# input_filter.net
KiCad netlist of a schematic drawn in Altium Designer
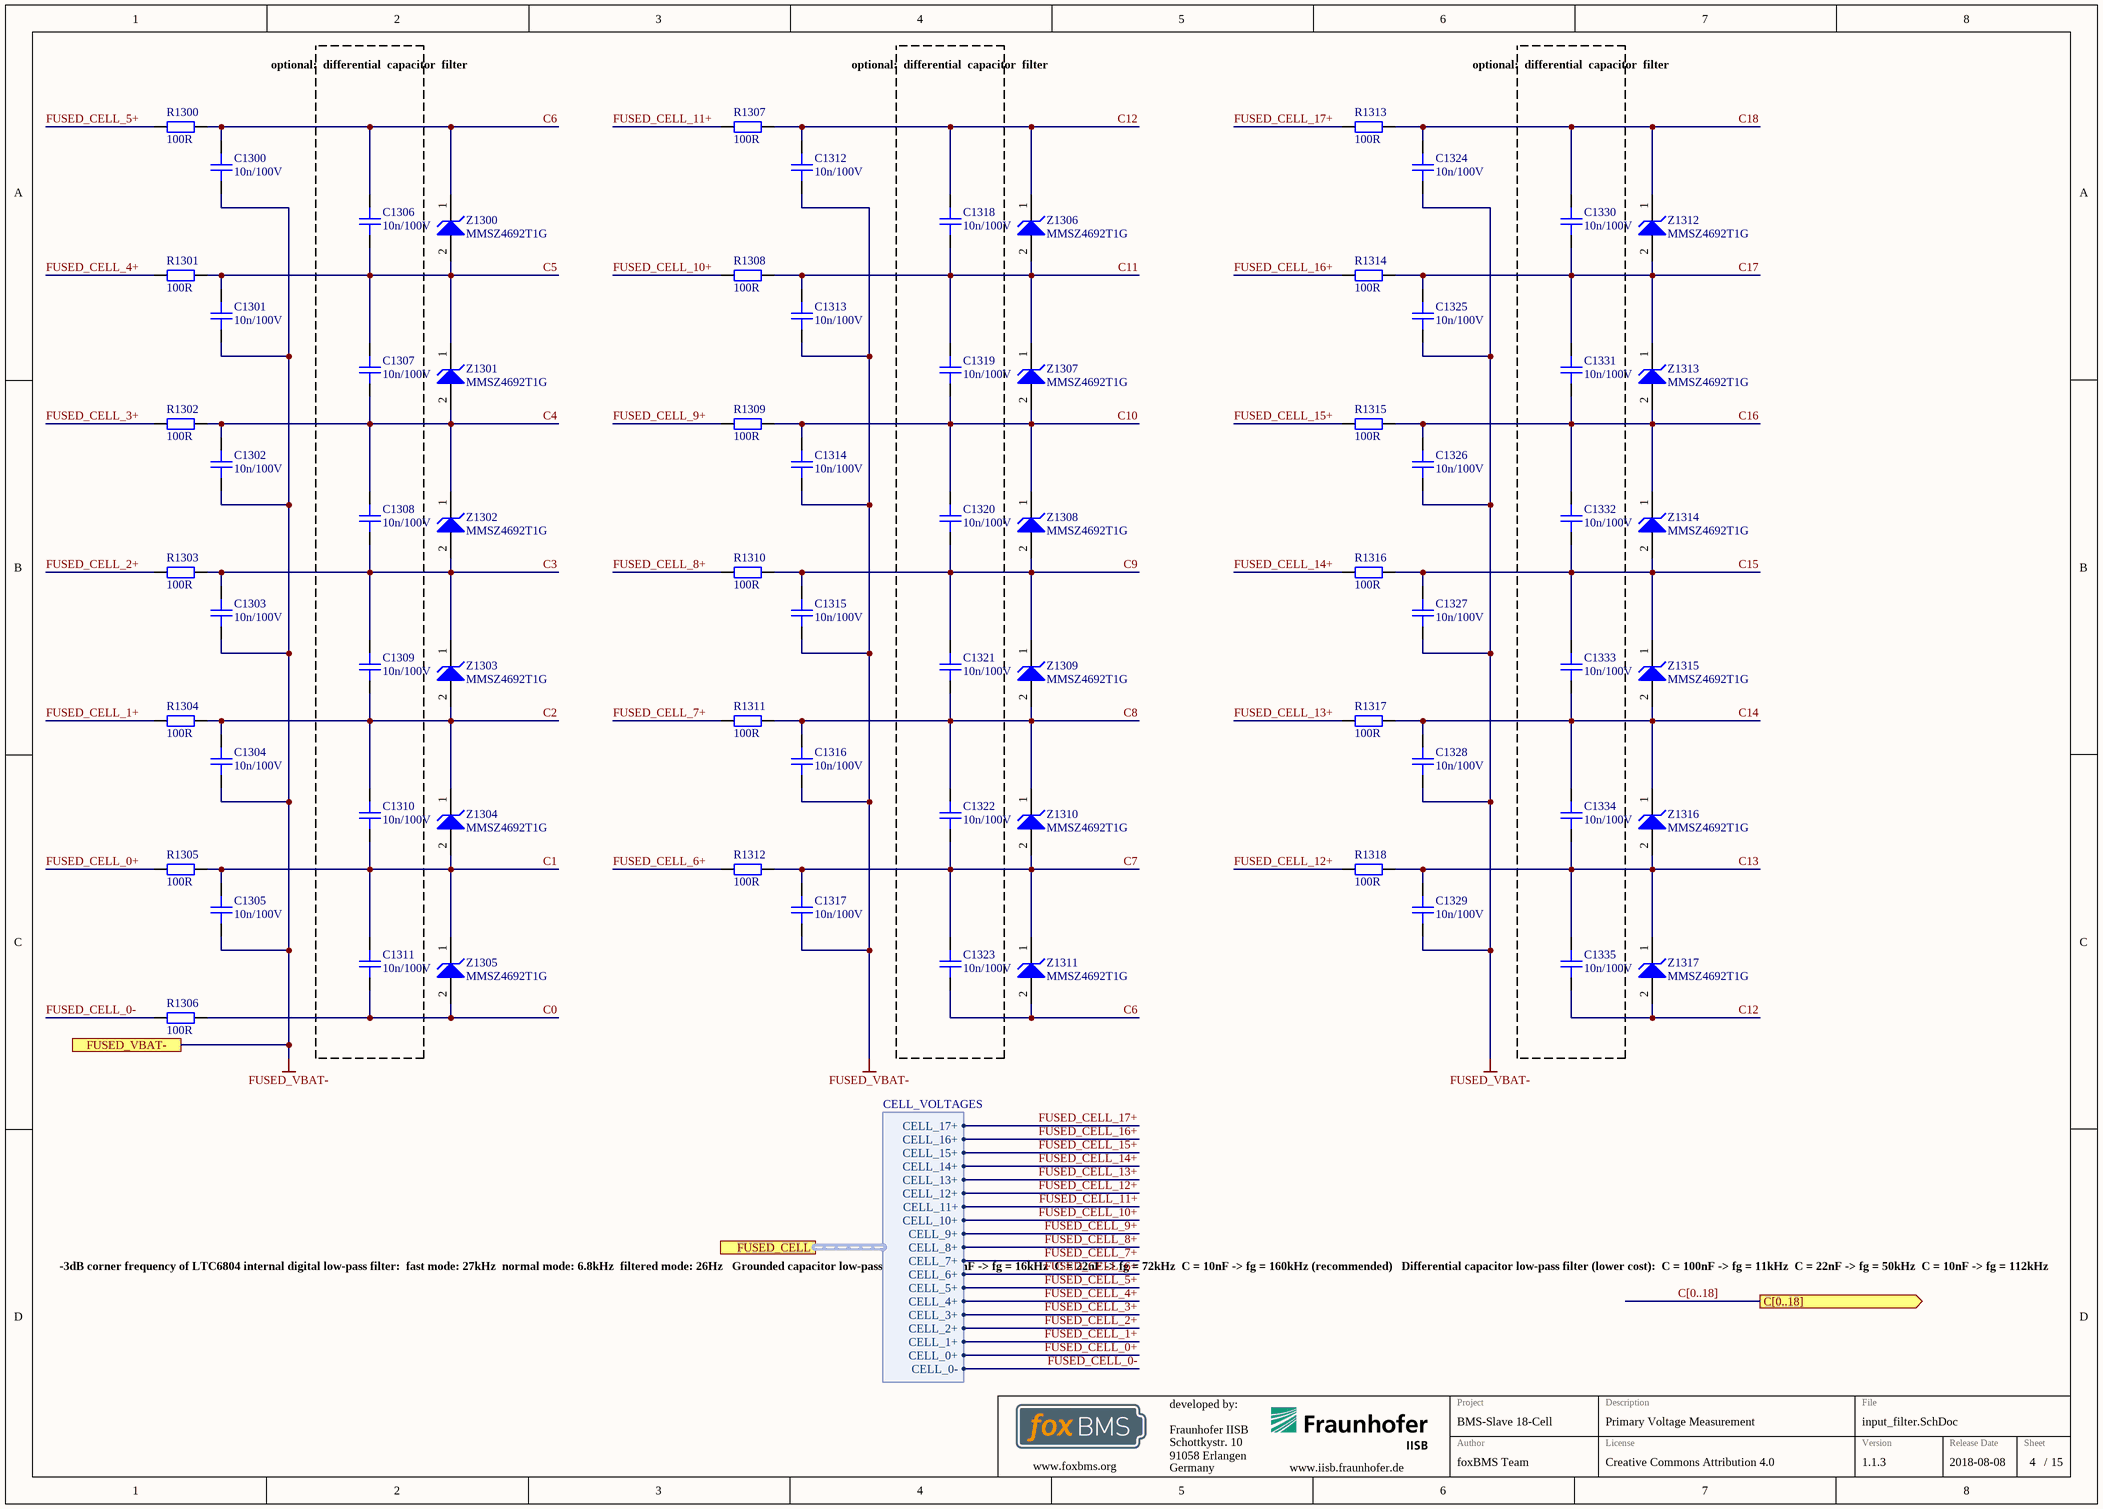
[diagram p0: input_filter.SchDoc]

(export (version "E")
  (design (tool "Eeschema 10.0.6"))
  (components
    (comp (ref "C1300")
      (value "10n/100V")
      (footprint "CAPC1608X08N")
      (description "MLCC")
      (fields (field (name "PART NUMBER") "gen_C_ceramic_10n_100V_X7R_0603"))
      (libsource (lib "OE750") (part "C"))
    )
    (comp (ref "C1301")
      (value "10n/100V")
      (footprint "CAPC1608X08N")
      (description "MLCC")
      (fields (field (name "PART NUMBER") "gen_C_ceramic_10n_100V_X7R_0603"))
      (libsource (lib "OE750") (part "C"))
    )
    (comp (ref "C1302")
      (value "10n/100V")
      (footprint "CAPC1608X08N")
      (description "MLCC")
      (fields (field (name "PART NUMBER") "gen_C_ceramic_10n_100V_X7R_0603"))
      (libsource (lib "OE750") (part "C"))
    )
    (comp (ref "C1303")
      (value "10n/100V")
      (footprint "CAPC1608X08N")
      (description "MLCC")
      (fields (field (name "PART NUMBER") "gen_C_ceramic_10n_100V_X7R_0603"))
      (libsource (lib "OE750") (part "C"))
    )
    (comp (ref "C1304")
      (value "10n/100V")
      (footprint "CAPC1608X08N")
      (description "MLCC")
      (fields (field (name "PART NUMBER") "gen_C_ceramic_10n_100V_X7R_0603"))
      (libsource (lib "OE750") (part "C"))
    )
    (comp (ref "C1305")
      (value "10n/100V")
      (footprint "CAPC1608X08N")
      (description "MLCC")
      (fields (field (name "PART NUMBER") "gen_C_ceramic_10n_100V_X7R_0603"))
      (libsource (lib "OE750") (part "C"))
    )
    (comp (ref "C1306")
      (value "10n/100V")
      (footprint "CAPC1608X08N")
      (description "MLCC")
      (fields (field (name "PART NUMBER") "gen_C_ceramic_10n_100V_X7R_0603"))
      (libsource (lib "OE750") (part "C"))
    )
    (comp (ref "C1307")
      (value "10n/100V")
      (footprint "CAPC1608X08N")
      (description "MLCC")
      (fields (field (name "PART NUMBER") "gen_C_ceramic_10n_100V_X7R_0603"))
      (libsource (lib "OE750") (part "C"))
    )
    (comp (ref "C1308")
      (value "10n/100V")
      (footprint "CAPC1608X08N")
      (description "MLCC")
      (fields (field (name "PART NUMBER") "gen_C_ceramic_10n_100V_X7R_0603"))
      (libsource (lib "OE750") (part "C"))
    )
    (comp (ref "C1309")
      (value "10n/100V")
      (footprint "CAPC1608X08N")
      (description "MLCC")
      (fields (field (name "PART NUMBER") "gen_C_ceramic_10n_100V_X7R_0603"))
      (libsource (lib "OE750") (part "C"))
    )
    (comp (ref "C1310")
      (value "10n/100V")
      (footprint "CAPC1608X08N")
      (description "MLCC")
      (fields (field (name "PART NUMBER") "gen_C_ceramic_10n_100V_X7R_0603"))
      (libsource (lib "OE750") (part "C"))
    )
    (comp (ref "C1311")
      (value "10n/100V")
      (footprint "CAPC1608X08N")
      (description "MLCC")
      (fields (field (name "PART NUMBER") "gen_C_ceramic_10n_100V_X7R_0603"))
      (libsource (lib "OE750") (part "C"))
    )
    (comp (ref "C1312")
      (value "10n/100V")
      (footprint "CAPC1608X08N")
      (description "MLCC")
      (fields (field (name "PART NUMBER") "gen_C_ceramic_10n_100V_X7R_0603"))
      (libsource (lib "OE750") (part "C"))
    )
    (comp (ref "C1313")
      (value "10n/100V")
      (footprint "CAPC1608X08N")
      (description "MLCC")
      (fields (field (name "PART NUMBER") "gen_C_ceramic_10n_100V_X7R_0603"))
      (libsource (lib "OE750") (part "C"))
    )
    (comp (ref "C1314")
      (value "10n/100V")
      (footprint "CAPC1608X08N")
      (description "MLCC")
      (fields (field (name "PART NUMBER") "gen_C_ceramic_10n_100V_X7R_0603"))
      (libsource (lib "OE750") (part "C"))
    )
    (comp (ref "C1315")
      (value "10n/100V")
      (footprint "CAPC1608X08N")
      (description "MLCC")
      (fields (field (name "PART NUMBER") "gen_C_ceramic_10n_100V_X7R_0603"))
      (libsource (lib "OE750") (part "C"))
    )
    (comp (ref "C1316")
      (value "10n/100V")
      (footprint "CAPC1608X08N")
      (description "MLCC")
      (fields (field (name "PART NUMBER") "gen_C_ceramic_10n_100V_X7R_0603"))
      (libsource (lib "OE750") (part "C"))
    )
    (comp (ref "C1317")
      (value "10n/100V")
      (footprint "CAPC1608X08N")
      (description "MLCC")
      (fields (field (name "PART NUMBER") "gen_C_ceramic_10n_100V_X7R_0603"))
      (libsource (lib "OE750") (part "C"))
    )
    (comp (ref "C1318")
      (value "10n/100V")
      (footprint "CAPC1608X08N")
      (description "MLCC")
      (fields (field (name "PART NUMBER") "gen_C_ceramic_10n_100V_X7R_0603"))
      (libsource (lib "OE750") (part "C"))
    )
    (comp (ref "C1319")
      (value "10n/100V")
      (footprint "CAPC1608X08N")
      (description "MLCC")
      (fields (field (name "PART NUMBER") "gen_C_ceramic_10n_100V_X7R_0603"))
      (libsource (lib "OE750") (part "C"))
    )
    (comp (ref "C1320")
      (value "10n/100V")
      (footprint "CAPC1608X08N")
      (description "MLCC")
      (fields (field (name "PART NUMBER") "gen_C_ceramic_10n_100V_X7R_0603"))
      (libsource (lib "OE750") (part "C"))
    )
    (comp (ref "C1321")
      (value "10n/100V")
      (footprint "CAPC1608X08N")
      (description "MLCC")
      (fields (field (name "PART NUMBER") "gen_C_ceramic_10n_100V_X7R_0603"))
      (libsource (lib "OE750") (part "C"))
    )
    (comp (ref "C1322")
      (value "10n/100V")
      (footprint "CAPC1608X08N")
      (description "MLCC")
      (fields (field (name "PART NUMBER") "gen_C_ceramic_10n_100V_X7R_0603"))
      (libsource (lib "OE750") (part "C"))
    )
    (comp (ref "C1323")
      (value "10n/100V")
      (footprint "CAPC1608X08N")
      (description "MLCC")
      (fields (field (name "PART NUMBER") "gen_C_ceramic_10n_100V_X7R_0603"))
      (libsource (lib "OE750") (part "C"))
    )
    (comp (ref "C1324")
      (value "10n/100V")
      (footprint "CAPC1608X08N")
      (description "MLCC")
      (fields (field (name "PART NUMBER") "gen_C_ceramic_10n_100V_X7R_0603"))
      (libsource (lib "OE750") (part "C"))
    )
    (comp (ref "C1325")
      (value "10n/100V")
      (footprint "CAPC1608X08N")
      (description "MLCC")
      (fields (field (name "PART NUMBER") "gen_C_ceramic_10n_100V_X7R_0603"))
      (libsource (lib "OE750") (part "C"))
    )
    (comp (ref "C1326")
      (value "10n/100V")
      (footprint "CAPC1608X08N")
      (description "MLCC")
      (fields (field (name "PART NUMBER") "gen_C_ceramic_10n_100V_X7R_0603"))
      (libsource (lib "OE750") (part "C"))
    )
    (comp (ref "C1327")
      (value "10n/100V")
      (footprint "CAPC1608X08N")
      (description "MLCC")
      (fields (field (name "PART NUMBER") "gen_C_ceramic_10n_100V_X7R_0603"))
      (libsource (lib "OE750") (part "C"))
    )
    (comp (ref "C1328")
      (value "10n/100V")
      (footprint "CAPC1608X08N")
      (description "MLCC")
      (fields (field (name "PART NUMBER") "gen_C_ceramic_10n_100V_X7R_0603"))
      (libsource (lib "OE750") (part "C"))
    )
    (comp (ref "C1329")
      (value "10n/100V")
      (footprint "CAPC1608X08N")
      (description "MLCC")
      (fields (field (name "PART NUMBER") "gen_C_ceramic_10n_100V_X7R_0603"))
      (libsource (lib "OE750") (part "C"))
    )
    (comp (ref "C1330")
      (value "10n/100V")
      (footprint "CAPC1608X08N")
      (description "MLCC")
      (fields (field (name "PART NUMBER") "gen_C_ceramic_10n_100V_X7R_0603"))
      (libsource (lib "OE750") (part "C"))
    )
    (comp (ref "C1331")
      (value "10n/100V")
      (footprint "CAPC1608X08N")
      (description "MLCC")
      (fields (field (name "PART NUMBER") "gen_C_ceramic_10n_100V_X7R_0603"))
      (libsource (lib "OE750") (part "C"))
    )
    (comp (ref "C1332")
      (value "10n/100V")
      (footprint "CAPC1608X08N")
      (description "MLCC")
      (fields (field (name "PART NUMBER") "gen_C_ceramic_10n_100V_X7R_0603"))
      (libsource (lib "OE750") (part "C"))
    )
    (comp (ref "C1333")
      (value "10n/100V")
      (footprint "CAPC1608X08N")
      (description "MLCC")
      (fields (field (name "PART NUMBER") "gen_C_ceramic_10n_100V_X7R_0603"))
      (libsource (lib "OE750") (part "C"))
    )
    (comp (ref "C1334")
      (value "10n/100V")
      (footprint "CAPC1608X08N")
      (description "MLCC")
      (fields (field (name "PART NUMBER") "gen_C_ceramic_10n_100V_X7R_0603"))
      (libsource (lib "OE750") (part "C"))
    )
    (comp (ref "C1335")
      (value "10n/100V")
      (footprint "CAPC1608X08N")
      (description "MLCC")
      (fields (field (name "PART NUMBER") "gen_C_ceramic_10n_100V_X7R_0603"))
      (libsource (lib "OE750") (part "C"))
    )
    (comp (ref "R1300")
      (value "100R")
      (footprint "RESC1608X05N")
      (description "SMD Resistor 100R 0603")
      (fields (field (name "PART NUMBER") "gen_R_100R_0603") (field (name "TOLERANCE") "1%"))
      (libsource (lib "OE750") (part "R"))
    )
    (comp (ref "R1301")
      (value "100R")
      (footprint "RESC1608X05N")
      (description "SMD Resistor 100R 0603")
      (fields (field (name "PART NUMBER") "gen_R_100R_0603") (field (name "TOLERANCE") "1%"))
      (libsource (lib "OE750") (part "R"))
    )
    (comp (ref "R1302")
      (value "100R")
      (footprint "RESC1608X05N")
      (description "SMD Resistor 100R 0603")
      (fields (field (name "PART NUMBER") "gen_R_100R_0603") (field (name "TOLERANCE") "1%"))
      (libsource (lib "OE750") (part "R"))
    )
    (comp (ref "R1303")
      (value "100R")
      (footprint "RESC1608X05N")
      (description "SMD Resistor 100R 0603")
      (fields (field (name "PART NUMBER") "gen_R_100R_0603") (field (name "TOLERANCE") "1%"))
      (libsource (lib "OE750") (part "R"))
    )
    (comp (ref "R1304")
      (value "100R")
      (footprint "RESC1608X05N")
      (description "SMD Resistor 100R 0603")
      (fields (field (name "PART NUMBER") "gen_R_100R_0603") (field (name "TOLERANCE") "1%"))
      (libsource (lib "OE750") (part "R"))
    )
    (comp (ref "R1305")
      (value "100R")
      (footprint "RESC1608X05N")
      (description "SMD Resistor 100R 0603")
      (fields (field (name "PART NUMBER") "gen_R_100R_0603") (field (name "TOLERANCE") "1%"))
      (libsource (lib "OE750") (part "R"))
    )
    (comp (ref "R1306")
      (value "100R")
      (footprint "RESC1608X05N")
      (description "SMD Resistor 100R 0603")
      (fields (field (name "PART NUMBER") "gen_R_100R_0603") (field (name "TOLERANCE") "1%"))
      (libsource (lib "OE750") (part "R"))
    )
    (comp (ref "R1307")
      (value "100R")
      (footprint "RESC1608X05N")
      (description "SMD Resistor 100R 0603")
      (fields (field (name "PART NUMBER") "gen_R_100R_0603") (field (name "TOLERANCE") "1%"))
      (libsource (lib "OE750") (part "R"))
    )
    (comp (ref "R1308")
      (value "100R")
      (footprint "RESC1608X05N")
      (description "SMD Resistor 100R 0603")
      (fields (field (name "PART NUMBER") "gen_R_100R_0603") (field (name "TOLERANCE") "1%"))
      (libsource (lib "OE750") (part "R"))
    )
    (comp (ref "R1309")
      (value "100R")
      (footprint "RESC1608X05N")
      (description "SMD Resistor 100R 0603")
      (fields (field (name "PART NUMBER") "gen_R_100R_0603") (field (name "TOLERANCE") "1%"))
      (libsource (lib "OE750") (part "R"))
    )
    (comp (ref "R1310")
      (value "100R")
      (footprint "RESC1608X05N")
      (description "SMD Resistor 100R 0603")
      (fields (field (name "PART NUMBER") "gen_R_100R_0603") (field (name "TOLERANCE") "1%"))
      (libsource (lib "OE750") (part "R"))
    )
    (comp (ref "R1311")
      (value "100R")
      (footprint "RESC1608X05N")
      (description "SMD Resistor 100R 0603")
      (fields (field (name "PART NUMBER") "gen_R_100R_0603") (field (name "TOLERANCE") "1%"))
      (libsource (lib "OE750") (part "R"))
    )
    (comp (ref "R1312")
      (value "100R")
      (footprint "RESC1608X05N")
      (description "SMD Resistor 100R 0603")
      (fields (field (name "PART NUMBER") "gen_R_100R_0603") (field (name "TOLERANCE") "1%"))
      (libsource (lib "OE750") (part "R"))
    )
    (comp (ref "R1313")
      (value "100R")
      (footprint "RESC1608X05N")
      (description "SMD Resistor 100R 0603")
      (fields (field (name "PART NUMBER") "gen_R_100R_0603") (field (name "TOLERANCE") "1%"))
      (libsource (lib "OE750") (part "R"))
    )
    (comp (ref "R1314")
      (value "100R")
      (footprint "RESC1608X05N")
      (description "SMD Resistor 100R 0603")
      (fields (field (name "PART NUMBER") "gen_R_100R_0603") (field (name "TOLERANCE") "1%"))
      (libsource (lib "OE750") (part "R"))
    )
    (comp (ref "R1315")
      (value "100R")
      (footprint "RESC1608X05N")
      (description "SMD Resistor 100R 0603")
      (fields (field (name "PART NUMBER") "gen_R_100R_0603") (field (name "TOLERANCE") "1%"))
      (libsource (lib "OE750") (part "R"))
    )
    (comp (ref "R1316")
      (value "100R")
      (footprint "RESC1608X05N")
      (description "SMD Resistor 100R 0603")
      (fields (field (name "PART NUMBER") "gen_R_100R_0603") (field (name "TOLERANCE") "1%"))
      (libsource (lib "OE750") (part "R"))
    )
    (comp (ref "R1317")
      (value "100R")
      (footprint "RESC1608X05N")
      (description "SMD Resistor 100R 0603")
      (fields (field (name "PART NUMBER") "gen_R_100R_0603") (field (name "TOLERANCE") "1%"))
      (libsource (lib "OE750") (part "R"))
    )
    (comp (ref "R1318")
      (value "100R")
      (footprint "RESC1608X05N")
      (description "SMD Resistor 100R 0603")
      (fields (field (name "PART NUMBER") "gen_R_100R_0603") (field (name "TOLERANCE") "1%"))
      (libsource (lib "OE750") (part "R"))
    )
    (comp (ref "Z1300")
      (value "MMSZ4692T1G")
      (footprint "ONSC-SOD-123-2-425-04_V")
      (description "Zener Voltage Regulator, 500 mW, 2-Pin SOD-123, Pb-Free, Tape and Reel")
      (fields (field (name "MANUFACTURER") "On Semiconductor"))
      (libsource (lib "Altium Content Vault") (part "ONSC-K1A2-2"))
    )
    (comp (ref "Z1301")
      (value "MMSZ4692T1G")
      (footprint "ONSC-SOD-123-2-425-04_V")
      (description "Zener Voltage Regulator, 500 mW, 2-Pin SOD-123, Pb-Free, Tape and Reel")
      (fields (field (name "MANUFACTURER") "On Semiconductor"))
      (libsource (lib "Altium Content Vault") (part "ONSC-K1A2-2"))
    )
    (comp (ref "Z1302")
      (value "MMSZ4692T1G")
      (footprint "ONSC-SOD-123-2-425-04_V")
      (description "Zener Voltage Regulator, 500 mW, 2-Pin SOD-123, Pb-Free, Tape and Reel")
      (fields (field (name "MANUFACTURER") "On Semiconductor"))
      (libsource (lib "Altium Content Vault") (part "ONSC-K1A2-2"))
    )
    (comp (ref "Z1303")
      (value "MMSZ4692T1G")
      (footprint "ONSC-SOD-123-2-425-04_V")
      (description "Zener Voltage Regulator, 500 mW, 2-Pin SOD-123, Pb-Free, Tape and Reel")
      (fields (field (name "MANUFACTURER") "On Semiconductor"))
      (libsource (lib "Altium Content Vault") (part "ONSC-K1A2-2"))
    )
    (comp (ref "Z1304")
      (value "MMSZ4692T1G")
      (footprint "ONSC-SOD-123-2-425-04_V")
      (description "Zener Voltage Regulator, 500 mW, 2-Pin SOD-123, Pb-Free, Tape and Reel")
      (fields (field (name "MANUFACTURER") "On Semiconductor"))
      (libsource (lib "Altium Content Vault") (part "ONSC-K1A2-2"))
    )
    (comp (ref "Z1305")
      (value "MMSZ4692T1G")
      (footprint "ONSC-SOD-123-2-425-04_V")
      (description "Zener Voltage Regulator, 500 mW, 2-Pin SOD-123, Pb-Free, Tape and Reel")
      (fields (field (name "MANUFACTURER") "On Semiconductor"))
      (libsource (lib "Altium Content Vault") (part "ONSC-K1A2-2"))
    )
    (comp (ref "Z1306")
      (value "MMSZ4692T1G")
      (footprint "ONSC-SOD-123-2-425-04_V")
      (description "Zener Voltage Regulator, 500 mW, 2-Pin SOD-123, Pb-Free, Tape and Reel")
      (fields (field (name "MANUFACTURER") "On Semiconductor"))
      (libsource (lib "Altium Content Vault") (part "ONSC-K1A2-2"))
    )
    (comp (ref "Z1307")
      (value "MMSZ4692T1G")
      (footprint "ONSC-SOD-123-2-425-04_V")
      (description "Zener Voltage Regulator, 500 mW, 2-Pin SOD-123, Pb-Free, Tape and Reel")
      (fields (field (name "MANUFACTURER") "On Semiconductor"))
      (libsource (lib "Altium Content Vault") (part "ONSC-K1A2-2"))
    )
    (comp (ref "Z1308")
      (value "MMSZ4692T1G")
      (footprint "ONSC-SOD-123-2-425-04_V")
      (description "Zener Voltage Regulator, 500 mW, 2-Pin SOD-123, Pb-Free, Tape and Reel")
      (fields (field (name "MANUFACTURER") "On Semiconductor"))
      (libsource (lib "Altium Content Vault") (part "ONSC-K1A2-2"))
    )
    (comp (ref "Z1309")
      (value "MMSZ4692T1G")
      (footprint "ONSC-SOD-123-2-425-04_V")
      (description "Zener Voltage Regulator, 500 mW, 2-Pin SOD-123, Pb-Free, Tape and Reel")
      (fields (field (name "MANUFACTURER") "On Semiconductor"))
      (libsource (lib "Altium Content Vault") (part "ONSC-K1A2-2"))
    )
    (comp (ref "Z1310")
      (value "MMSZ4692T1G")
      (footprint "ONSC-SOD-123-2-425-04_V")
      (description "Zener Voltage Regulator, 500 mW, 2-Pin SOD-123, Pb-Free, Tape and Reel")
      (fields (field (name "MANUFACTURER") "On Semiconductor"))
      (libsource (lib "Altium Content Vault") (part "ONSC-K1A2-2"))
    )
    (comp (ref "Z1311")
      (value "MMSZ4692T1G")
      (footprint "ONSC-SOD-123-2-425-04_V")
      (description "Zener Voltage Regulator, 500 mW, 2-Pin SOD-123, Pb-Free, Tape and Reel")
      (fields (field (name "MANUFACTURER") "On Semiconductor"))
      (libsource (lib "Altium Content Vault") (part "ONSC-K1A2-2"))
    )
    (comp (ref "Z1312")
      (value "MMSZ4692T1G")
      (footprint "ONSC-SOD-123-2-425-04_V")
      (description "Zener Voltage Regulator, 500 mW, 2-Pin SOD-123, Pb-Free, Tape and Reel")
      (fields (field (name "MANUFACTURER") "On Semiconductor"))
      (libsource (lib "Altium Content Vault") (part "ONSC-K1A2-2"))
    )
    (comp (ref "Z1313")
      (value "MMSZ4692T1G")
      (footprint "ONSC-SOD-123-2-425-04_V")
      (description "Zener Voltage Regulator, 500 mW, 2-Pin SOD-123, Pb-Free, Tape and Reel")
      (fields (field (name "MANUFACTURER") "On Semiconductor"))
      (libsource (lib "Altium Content Vault") (part "ONSC-K1A2-2"))
    )
    (comp (ref "Z1314")
      (value "MMSZ4692T1G")
      (footprint "ONSC-SOD-123-2-425-04_V")
      (description "Zener Voltage Regulator, 500 mW, 2-Pin SOD-123, Pb-Free, Tape and Reel")
      (fields (field (name "MANUFACTURER") "On Semiconductor"))
      (libsource (lib "Altium Content Vault") (part "ONSC-K1A2-2"))
    )
    (comp (ref "Z1315")
      (value "MMSZ4692T1G")
      (footprint "ONSC-SOD-123-2-425-04_V")
      (description "Zener Voltage Regulator, 500 mW, 2-Pin SOD-123, Pb-Free, Tape and Reel")
      (fields (field (name "MANUFACTURER") "On Semiconductor"))
      (libsource (lib "Altium Content Vault") (part "ONSC-K1A2-2"))
    )
    (comp (ref "Z1316")
      (value "MMSZ4692T1G")
      (footprint "ONSC-SOD-123-2-425-04_V")
      (description "Zener Voltage Regulator, 500 mW, 2-Pin SOD-123, Pb-Free, Tape and Reel")
      (fields (field (name "MANUFACTURER") "On Semiconductor"))
      (libsource (lib "Altium Content Vault") (part "ONSC-K1A2-2"))
    )
    (comp (ref "Z1317")
      (value "MMSZ4692T1G")
      (footprint "ONSC-SOD-123-2-425-04_V")
      (description "Zener Voltage Regulator, 500 mW, 2-Pin SOD-123, Pb-Free, Tape and Reel")
      (fields (field (name "MANUFACTURER") "On Semiconductor"))
      (libsource (lib "Altium Content Vault") (part "ONSC-K1A2-2"))
    )
  )
  (nets
    (net (code "2") (name "/C0") (class "Default")
      (node (ref "C1311") (pin "2") (pinfunction "2_2") (pintype "passive"))
      (node (ref "R1306") (pin "2") (pinfunction "2_2") (pintype "passive"))
      (node (ref "Z1305") (pin "2") (pinfunction "A_2") (pintype "passive"))
    )
    (net (code "3") (name "/C1") (class "Default")
      (node (ref "C1305") (pin "1") (pinfunction "1_1") (pintype "passive"))
      (node (ref "C1310") (pin "2") (pinfunction "2_2") (pintype "passive"))
      (node (ref "C1311") (pin "1") (pinfunction "1_1") (pintype "passive"))
      (node (ref "R1305") (pin "2") (pinfunction "2_2") (pintype "passive"))
      (node (ref "Z1304") (pin "2") (pinfunction "A_2") (pintype "passive"))
      (node (ref "Z1305") (pin "1") (pinfunction "K_1") (pintype "passive"))
    )
    (net (code "4") (name "/C2") (class "Default")
      (node (ref "C1304") (pin "1") (pinfunction "1_1") (pintype "passive"))
      (node (ref "C1309") (pin "2") (pinfunction "2_2") (pintype "passive"))
      (node (ref "C1310") (pin "1") (pinfunction "1_1") (pintype "passive"))
      (node (ref "R1304") (pin "2") (pinfunction "2_2") (pintype "passive"))
      (node (ref "Z1303") (pin "2") (pinfunction "A_2") (pintype "passive"))
      (node (ref "Z1304") (pin "1") (pinfunction "K_1") (pintype "passive"))
    )
    (net (code "5") (name "/C3") (class "Default")
      (node (ref "C1303") (pin "1") (pinfunction "1_1") (pintype "passive"))
      (node (ref "C1308") (pin "2") (pinfunction "2_2") (pintype "passive"))
      (node (ref "C1309") (pin "1") (pinfunction "1_1") (pintype "passive"))
      (node (ref "R1303") (pin "2") (pinfunction "2_2") (pintype "passive"))
      (node (ref "Z1302") (pin "2") (pinfunction "A_2") (pintype "passive"))
      (node (ref "Z1303") (pin "1") (pinfunction "K_1") (pintype "passive"))
    )
    (net (code "6") (name "/C4") (class "Default")
      (node (ref "C1302") (pin "1") (pinfunction "1_1") (pintype "passive"))
      (node (ref "C1307") (pin "2") (pinfunction "2_2") (pintype "passive"))
      (node (ref "C1308") (pin "1") (pinfunction "1_1") (pintype "passive"))
      (node (ref "R1302") (pin "2") (pinfunction "2_2") (pintype "passive"))
      (node (ref "Z1301") (pin "2") (pinfunction "A_2") (pintype "passive"))
      (node (ref "Z1302") (pin "1") (pinfunction "K_1") (pintype "passive"))
    )
    (net (code "7") (name "/C5") (class "Default")
      (node (ref "C1301") (pin "1") (pinfunction "1_1") (pintype "passive"))
      (node (ref "C1306") (pin "2") (pinfunction "2_2") (pintype "passive"))
      (node (ref "C1307") (pin "1") (pinfunction "1_1") (pintype "passive"))
      (node (ref "R1301") (pin "2") (pinfunction "2_2") (pintype "passive"))
      (node (ref "Z1300") (pin "2") (pinfunction "A_2") (pintype "passive"))
      (node (ref "Z1301") (pin "1") (pinfunction "K_1") (pintype "passive"))
    )
    (net (code "8") (name "/C6") (class "Default")
      (node (ref "C1300") (pin "1") (pinfunction "1_1") (pintype "passive"))
      (node (ref "C1306") (pin "1") (pinfunction "1_1") (pintype "passive"))
      (node (ref "C1323") (pin "2") (pinfunction "2_2") (pintype "passive"))
      (node (ref "R1300") (pin "2") (pinfunction "2_2") (pintype "passive"))
      (node (ref "Z1300") (pin "1") (pinfunction "K_1") (pintype "passive"))
      (node (ref "Z1311") (pin "2") (pinfunction "A_2") (pintype "passive"))
    )
    (net (code "9") (name "/C7") (class "Default")
      (node (ref "C1317") (pin "1") (pinfunction "1_1") (pintype "passive"))
      (node (ref "C1322") (pin "2") (pinfunction "2_2") (pintype "passive"))
      (node (ref "C1323") (pin "1") (pinfunction "1_1") (pintype "passive"))
      (node (ref "R1312") (pin "2") (pinfunction "2_2") (pintype "passive"))
      (node (ref "Z1310") (pin "2") (pinfunction "A_2") (pintype "passive"))
      (node (ref "Z1311") (pin "1") (pinfunction "K_1") (pintype "passive"))
    )
    (net (code "10") (name "/C8") (class "Default")
      (node (ref "C1316") (pin "1") (pinfunction "1_1") (pintype "passive"))
      (node (ref "C1321") (pin "2") (pinfunction "2_2") (pintype "passive"))
      (node (ref "C1322") (pin "1") (pinfunction "1_1") (pintype "passive"))
      (node (ref "R1311") (pin "2") (pinfunction "2_2") (pintype "passive"))
      (node (ref "Z1309") (pin "2") (pinfunction "A_2") (pintype "passive"))
      (node (ref "Z1310") (pin "1") (pinfunction "K_1") (pintype "passive"))
    )
    (net (code "11") (name "/C9") (class "Default")
      (node (ref "C1315") (pin "1") (pinfunction "1_1") (pintype "passive"))
      (node (ref "C1320") (pin "2") (pinfunction "2_2") (pintype "passive"))
      (node (ref "C1321") (pin "1") (pinfunction "1_1") (pintype "passive"))
      (node (ref "R1310") (pin "2") (pinfunction "2_2") (pintype "passive"))
      (node (ref "Z1308") (pin "2") (pinfunction "A_2") (pintype "passive"))
      (node (ref "Z1309") (pin "1") (pinfunction "K_1") (pintype "passive"))
    )
    (net (code "12") (name "/C10") (class "Default")
      (node (ref "C1314") (pin "1") (pinfunction "1_1") (pintype "passive"))
      (node (ref "C1319") (pin "2") (pinfunction "2_2") (pintype "passive"))
      (node (ref "C1320") (pin "1") (pinfunction "1_1") (pintype "passive"))
      (node (ref "R1309") (pin "2") (pinfunction "2_2") (pintype "passive"))
      (node (ref "Z1307") (pin "2") (pinfunction "A_2") (pintype "passive"))
      (node (ref "Z1308") (pin "1") (pinfunction "K_1") (pintype "passive"))
    )
    (net (code "13") (name "/C11") (class "Default")
      (node (ref "C1313") (pin "1") (pinfunction "1_1") (pintype "passive"))
      (node (ref "C1318") (pin "2") (pinfunction "2_2") (pintype "passive"))
      (node (ref "C1319") (pin "1") (pinfunction "1_1") (pintype "passive"))
      (node (ref "R1308") (pin "2") (pinfunction "2_2") (pintype "passive"))
      (node (ref "Z1306") (pin "2") (pinfunction "A_2") (pintype "passive"))
      (node (ref "Z1307") (pin "1") (pinfunction "K_1") (pintype "passive"))
    )
    (net (code "14") (name "/C12") (class "Default")
      (node (ref "C1312") (pin "1") (pinfunction "1_1") (pintype "passive"))
      (node (ref "C1318") (pin "1") (pinfunction "1_1") (pintype "passive"))
      (node (ref "C1335") (pin "2") (pinfunction "2_2") (pintype "passive"))
      (node (ref "R1307") (pin "2") (pinfunction "2_2") (pintype "passive"))
      (node (ref "Z1306") (pin "1") (pinfunction "K_1") (pintype "passive"))
      (node (ref "Z1317") (pin "2") (pinfunction "A_2") (pintype "passive"))
    )
    (net (code "15") (name "/C13") (class "Default")
      (node (ref "C1329") (pin "1") (pinfunction "1_1") (pintype "passive"))
      (node (ref "C1334") (pin "2") (pinfunction "2_2") (pintype "passive"))
      (node (ref "C1335") (pin "1") (pinfunction "1_1") (pintype "passive"))
      (node (ref "R1318") (pin "2") (pinfunction "2_2") (pintype "passive"))
      (node (ref "Z1316") (pin "2") (pinfunction "A_2") (pintype "passive"))
      (node (ref "Z1317") (pin "1") (pinfunction "K_1") (pintype "passive"))
    )
    (net (code "16") (name "/C14") (class "Default")
      (node (ref "C1328") (pin "1") (pinfunction "1_1") (pintype "passive"))
      (node (ref "C1333") (pin "2") (pinfunction "2_2") (pintype "passive"))
      (node (ref "C1334") (pin "1") (pinfunction "1_1") (pintype "passive"))
      (node (ref "R1317") (pin "2") (pinfunction "2_2") (pintype "passive"))
      (node (ref "Z1315") (pin "2") (pinfunction "A_2") (pintype "passive"))
      (node (ref "Z1316") (pin "1") (pinfunction "K_1") (pintype "passive"))
    )
    (net (code "17") (name "/C15") (class "Default")
      (node (ref "C1327") (pin "1") (pinfunction "1_1") (pintype "passive"))
      (node (ref "C1332") (pin "2") (pinfunction "2_2") (pintype "passive"))
      (node (ref "C1333") (pin "1") (pinfunction "1_1") (pintype "passive"))
      (node (ref "R1316") (pin "2") (pinfunction "2_2") (pintype "passive"))
      (node (ref "Z1314") (pin "2") (pinfunction "A_2") (pintype "passive"))
      (node (ref "Z1315") (pin "1") (pinfunction "K_1") (pintype "passive"))
    )
    (net (code "18") (name "/C16") (class "Default")
      (node (ref "C1326") (pin "1") (pinfunction "1_1") (pintype "passive"))
      (node (ref "C1331") (pin "2") (pinfunction "2_2") (pintype "passive"))
      (node (ref "C1332") (pin "1") (pinfunction "1_1") (pintype "passive"))
      (node (ref "R1315") (pin "2") (pinfunction "2_2") (pintype "passive"))
      (node (ref "Z1313") (pin "2") (pinfunction "A_2") (pintype "passive"))
      (node (ref "Z1314") (pin "1") (pinfunction "K_1") (pintype "passive"))
    )
    (net (code "19") (name "/C17") (class "Default")
      (node (ref "C1325") (pin "1") (pinfunction "1_1") (pintype "passive"))
      (node (ref "C1330") (pin "2") (pinfunction "2_2") (pintype "passive"))
      (node (ref "C1331") (pin "1") (pinfunction "1_1") (pintype "passive"))
      (node (ref "R1314") (pin "2") (pinfunction "2_2") (pintype "passive"))
      (node (ref "Z1312") (pin "2") (pinfunction "A_2") (pintype "passive"))
      (node (ref "Z1313") (pin "1") (pinfunction "K_1") (pintype "passive"))
    )
    (net (code "20") (name "/C18") (class "Default")
      (node (ref "C1324") (pin "1") (pinfunction "1_1") (pintype "passive"))
      (node (ref "C1330") (pin "1") (pinfunction "1_1") (pintype "passive"))
      (node (ref "R1313") (pin "2") (pinfunction "2_2") (pintype "passive"))
      (node (ref "Z1312") (pin "1") (pinfunction "K_1") (pintype "passive"))
    )
    (net (code "22") (name "/FUSED_CELL_0+") (class "Default")
      (node (ref "R1305") (pin "1") (pinfunction "1_1") (pintype "passive"))
    )
    (net (code "23") (name "/FUSED_CELL_0-") (class "Default")
      (node (ref "R1306") (pin "1") (pinfunction "1_1") (pintype "passive"))
    )
    (net (code "24") (name "/FUSED_CELL_1+") (class "Default")
      (node (ref "R1304") (pin "1") (pinfunction "1_1") (pintype "passive"))
    )
    (net (code "25") (name "/FUSED_CELL_2+") (class "Default")
      (node (ref "R1303") (pin "1") (pinfunction "1_1") (pintype "passive"))
    )
    (net (code "26") (name "/FUSED_CELL_3+") (class "Default")
      (node (ref "R1302") (pin "1") (pinfunction "1_1") (pintype "passive"))
    )
    (net (code "27") (name "/FUSED_CELL_4+") (class "Default")
      (node (ref "R1301") (pin "1") (pinfunction "1_1") (pintype "passive"))
    )
    (net (code "28") (name "/FUSED_CELL_5+") (class "Default")
      (node (ref "R1300") (pin "1") (pinfunction "1_1") (pintype "passive"))
    )
    (net (code "29") (name "/FUSED_CELL_6+") (class "Default")
      (node (ref "R1312") (pin "1") (pinfunction "1_1") (pintype "passive"))
    )
    (net (code "30") (name "/FUSED_CELL_7+") (class "Default")
      (node (ref "R1311") (pin "1") (pinfunction "1_1") (pintype "passive"))
    )
    (net (code "31") (name "/FUSED_CELL_8+") (class "Default")
      (node (ref "R1310") (pin "1") (pinfunction "1_1") (pintype "passive"))
    )
    (net (code "32") (name "/FUSED_CELL_9+") (class "Default")
      (node (ref "R1309") (pin "1") (pinfunction "1_1") (pintype "passive"))
    )
    (net (code "33") (name "/FUSED_CELL_10+") (class "Default")
      (node (ref "R1308") (pin "1") (pinfunction "1_1") (pintype "passive"))
    )
    (net (code "34") (name "/FUSED_CELL_11+") (class "Default")
      (node (ref "R1307") (pin "1") (pinfunction "1_1") (pintype "passive"))
    )
    (net (code "35") (name "/FUSED_CELL_12+") (class "Default")
      (node (ref "R1318") (pin "1") (pinfunction "1_1") (pintype "passive"))
    )
    (net (code "36") (name "/FUSED_CELL_13+") (class "Default")
      (node (ref "R1317") (pin "1") (pinfunction "1_1") (pintype "passive"))
    )
    (net (code "37") (name "/FUSED_CELL_14+") (class "Default")
      (node (ref "R1316") (pin "1") (pinfunction "1_1") (pintype "passive"))
    )
    (net (code "38") (name "/FUSED_CELL_15+") (class "Default")
      (node (ref "R1315") (pin "1") (pinfunction "1_1") (pintype "passive"))
    )
    (net (code "39") (name "/FUSED_CELL_16+") (class "Default")
      (node (ref "R1314") (pin "1") (pinfunction "1_1") (pintype "passive"))
    )
    (net (code "40") (name "/FUSED_CELL_17+") (class "Default")
      (node (ref "R1313") (pin "1") (pinfunction "1_1") (pintype "passive"))
    )
    (net (code "42") (name "FUSED_VBAT-") (class "Default")
      (node (ref "C1300") (pin "2") (pinfunction "2_2") (pintype "passive"))
      (node (ref "C1301") (pin "2") (pinfunction "2_2") (pintype "passive"))
      (node (ref "C1302") (pin "2") (pinfunction "2_2") (pintype "passive"))
      (node (ref "C1303") (pin "2") (pinfunction "2_2") (pintype "passive"))
      (node (ref "C1304") (pin "2") (pinfunction "2_2") (pintype "passive"))
      (node (ref "C1305") (pin "2") (pinfunction "2_2") (pintype "passive"))
      (node (ref "C1312") (pin "2") (pinfunction "2_2") (pintype "passive"))
      (node (ref "C1313") (pin "2") (pinfunction "2_2") (pintype "passive"))
      (node (ref "C1314") (pin "2") (pinfunction "2_2") (pintype "passive"))
      (node (ref "C1315") (pin "2") (pinfunction "2_2") (pintype "passive"))
      (node (ref "C1316") (pin "2") (pinfunction "2_2") (pintype "passive"))
      (node (ref "C1317") (pin "2") (pinfunction "2_2") (pintype "passive"))
      (node (ref "C1324") (pin "2") (pinfunction "2_2") (pintype "passive"))
      (node (ref "C1325") (pin "2") (pinfunction "2_2") (pintype "passive"))
      (node (ref "C1326") (pin "2") (pinfunction "2_2") (pintype "passive"))
      (node (ref "C1327") (pin "2") (pinfunction "2_2") (pintype "passive"))
      (node (ref "C1328") (pin "2") (pinfunction "2_2") (pintype "passive"))
      (node (ref "C1329") (pin "2") (pinfunction "2_2") (pintype "passive"))
    )
  )
)
